# DM2080_RIGHT_OV9782.net
KiCad netlist of a schematic drawn in Altium Designer
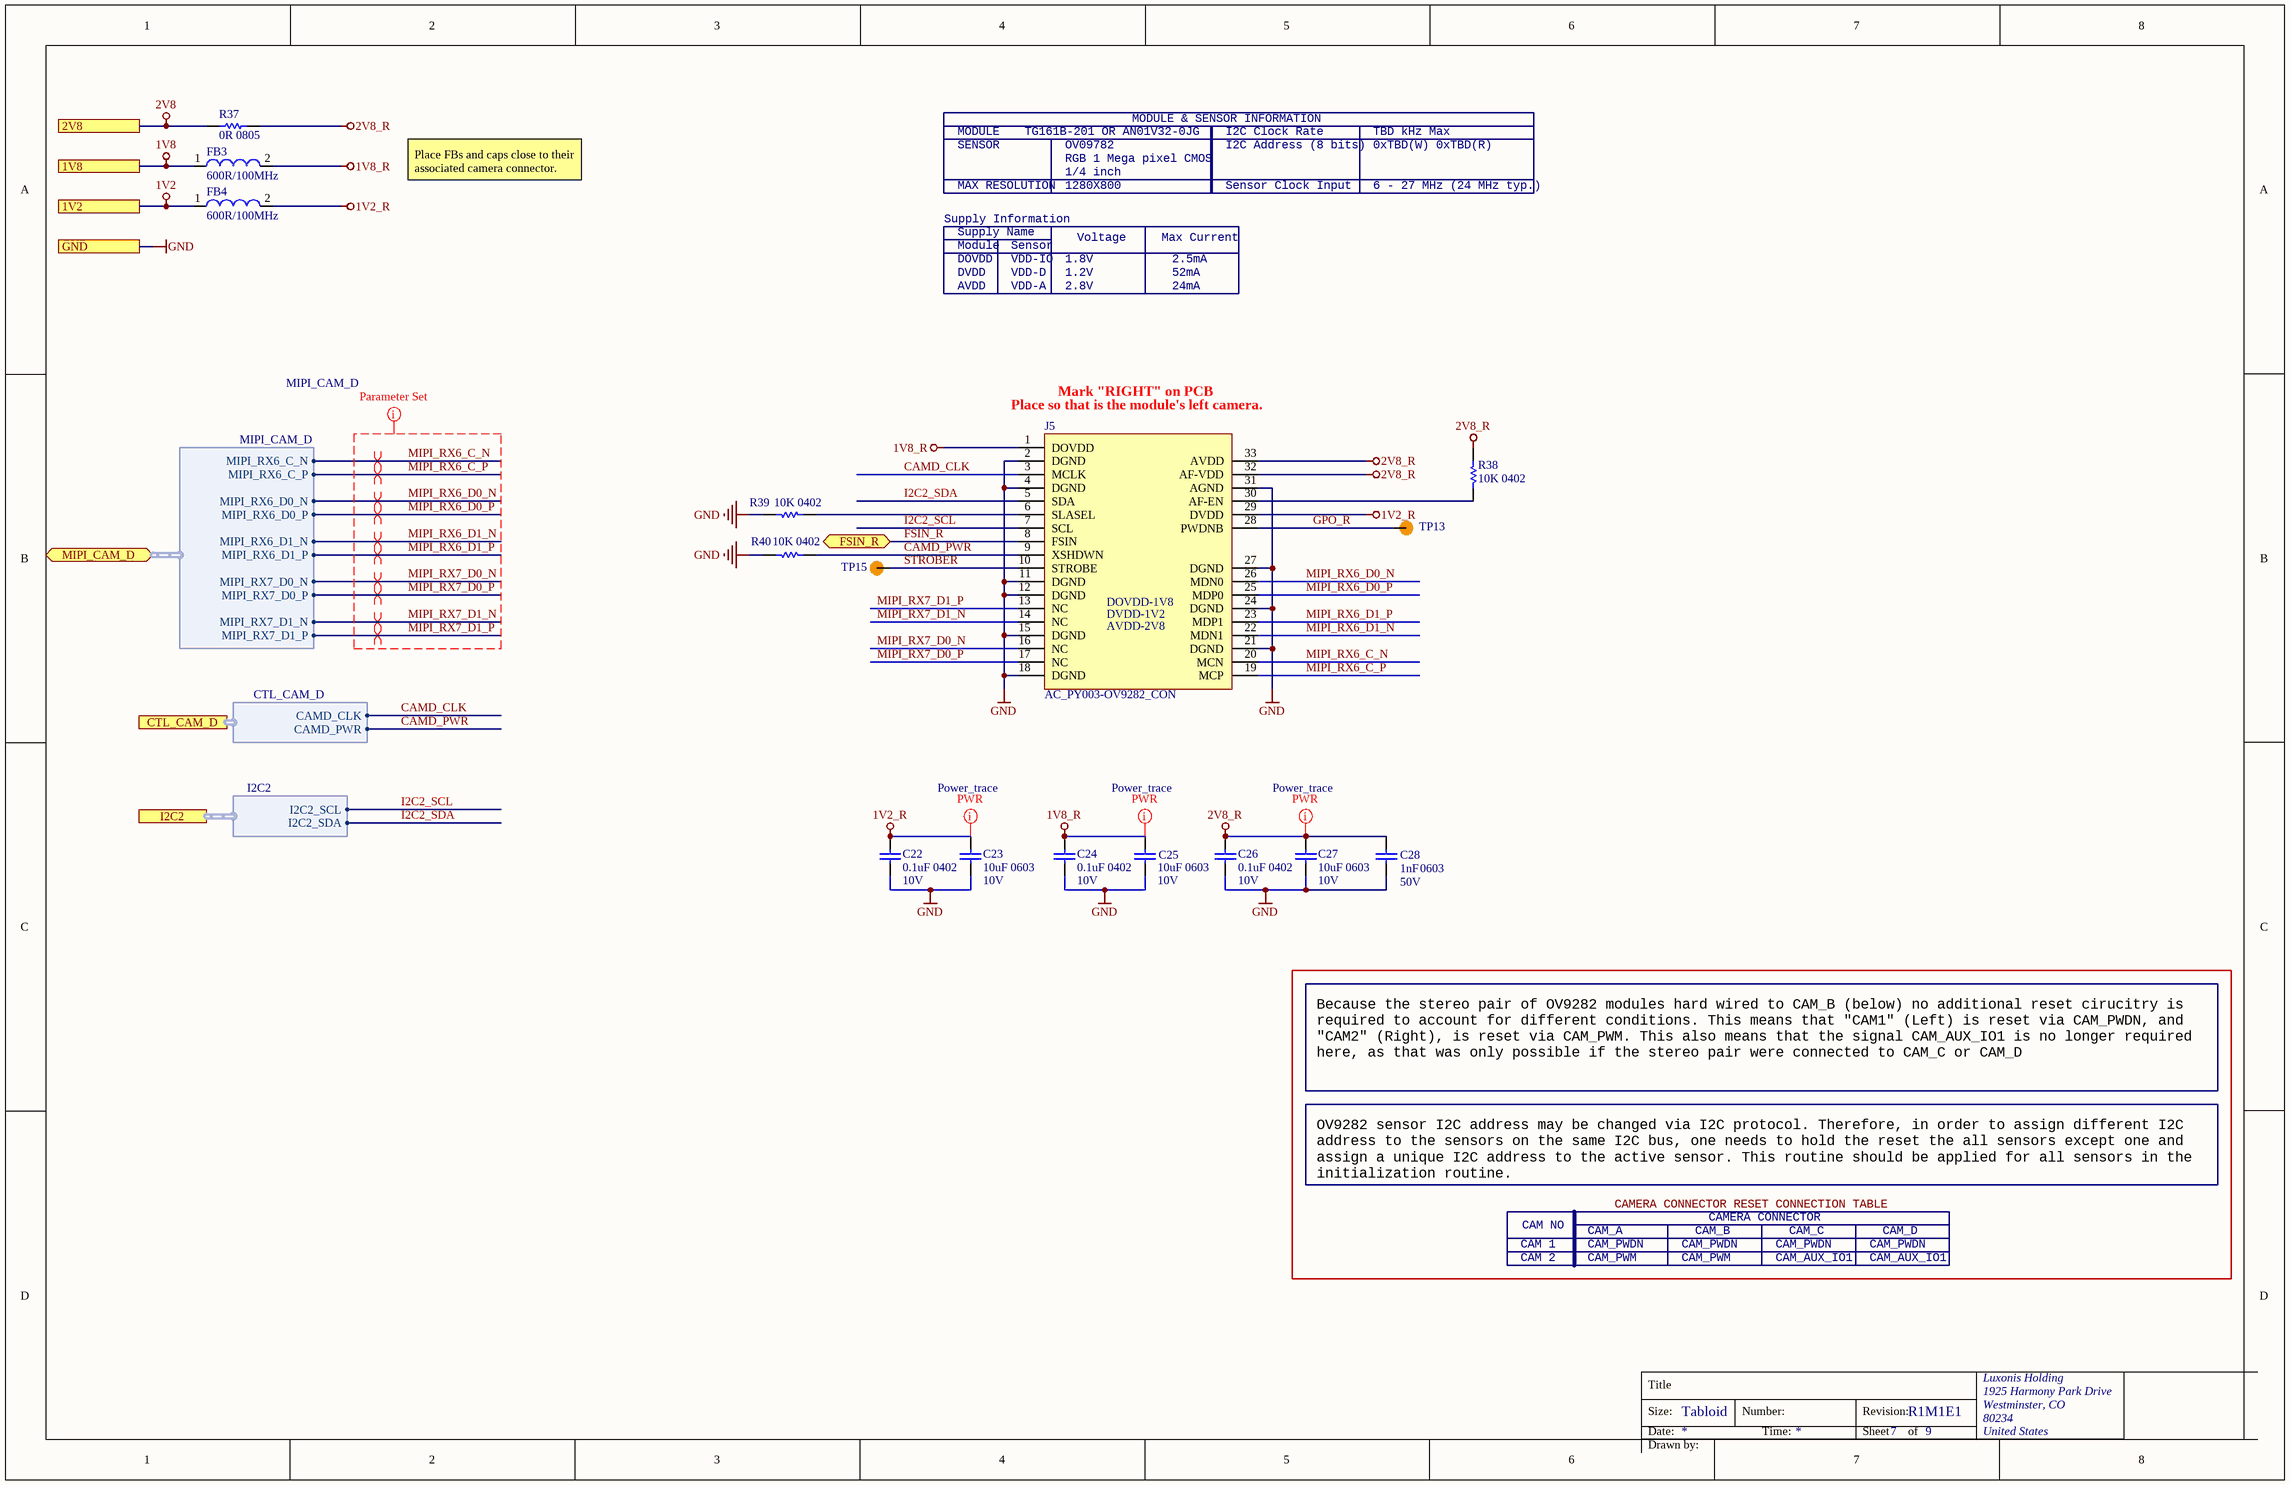
[diagram p0: DM2080_RIGHT_OV9782.SchDoc]

(export (version "E")
  (design (tool "Eeschema 10.0.6"))
  (components
    (comp (ref "C22")
      (value "0.1uF 0402")
      (footprint "CAP_Altium_Vault_Generic:CAPC0402(1005)70_L")
      (description "CAP CER 0.1UF 10V X7R 0402 5%")
      (fields (field (name "TOLERANCE") "5%") (field (name "VOLTAGE RATING") "10V"))
      (libsource (lib "LuxonisMaster") (part "GRM155R71A104JA01D"))
    )
    (comp (ref "C23")
      (value "10uF 0603")
      (footprint "CAP_Altium_Vault_Generic:CAPC0603(1608)100_L")
      (description "CAP CER 10UF 10V X5R 0603 20%")
      (fields (field (name "TOLERANCE") "20%") (field (name "VOLTAGE RATING") "10V"))
      (libsource (lib "LuxonisMaster") (part "GRM188R61A106ME69D"))
    )
    (comp (ref "C24")
      (value "0.1uF 0402")
      (footprint "CAP_Altium_Vault_Generic:CAPC0402(1005)70_L")
      (description "CAP CER 0.1UF 10V X7R 0402 5%")
      (fields (field (name "TOLERANCE") "5%") (field (name "VOLTAGE RATING") "10V"))
      (libsource (lib "LuxonisMaster") (part "GRM155R71A104JA01D"))
    )
    (comp (ref "C25")
      (value "10uF 0603")
      (footprint "CAP_Altium_Vault_Generic:CAPC0603(1608)100_L")
      (description "CAP CER 10UF 10V X5R 0603 20%")
      (fields (field (name "TOLERANCE") "20%") (field (name "VOLTAGE RATING") "10V"))
      (libsource (lib "LuxonisMaster") (part "GRM188R61A106ME69D"))
    )
    (comp (ref "C26")
      (value "0.1uF 0402")
      (footprint "CAP_Altium_Vault_Generic:CAPC0402(1005)70_L")
      (description "CAP CER 0.1UF 10V X7R 0402 5%")
      (fields (field (name "TOLERANCE") "5%") (field (name "VOLTAGE RATING") "10V"))
      (libsource (lib "LuxonisMaster") (part "GRM155R71A104JA01D"))
    )
    (comp (ref "C27")
      (value "10uF 0603")
      (footprint "CAP_Altium_Vault_Generic:CAPC0603(1608)100_L")
      (description "CAP CER 10UF 10V X5R 0603 20%")
      (fields (field (name "TOLERANCE") "20%") (field (name "VOLTAGE RATING") "10V"))
      (libsource (lib "LuxonisMaster") (part "GRM188R61A106ME69D"))
    )
    (comp (ref "C28")
      (value "1nF 0603 C0G")
      (footprint "CAP_Altium_Vault_Generic:CAPC0603(1608)100_L")
      (description "CAP CER 1000PF 50V C0G/NP0 0603")
      (fields
        (field (name "MANUFACTURER") "Murata")
        (field (name "MANUFACTURER PART NUMBER") "GRM1885C1H102FA01D")
        (field (name "CASE/PACKAGE") "0603")
        (field (name "CAPACITANCE") "1nF")
        (field (name "VOLTAGE RATING") "50V")
      )
      (libsource (lib "LuxonisMaster") (part "GRM1885C1H102FA01D"))
    )
    (comp (ref "FB3")
      (value "600R/100MHz")
      (footprint "LuxonisMaster:2508056017Y2")
      (description "FERRITE BEAD, 0.1OHM, 2A, 0805, 600R/100MHz")
      (fields (field (name "TOLERANCE") "25%"))
      (libsource (lib "LuxonisMaster") (part "2508056017Y2"))
    )
    (comp (ref "FB4")
      (value "600R/100MHz")
      (footprint "LuxonisMaster:2508056017Y2")
      (description "FERRITE BEAD, 0.1OHM, 2A, 0805, 600R/100MHz")
      (fields (field (name "TOLERANCE") "25%"))
      (libsource (lib "LuxonisMaster") (part "2508056017Y2"))
    )
    (comp (ref "J5")
      (value "AC_PY003-OV9282_CON")
      (footprint "AC-PY003-OV9282")
      (description "FFC/FPC Connector, 33 Contact(s), 1 Row(s), Female, Right Angle, Surface Mount Terminal")
      (libsource (lib "Luxonis LLC") (part "AC_PY003-OV9282_CON"))
    )
    (comp (ref "R37")
      (value "0R 0805")
      (footprint "RESC0805(2012)_L")
      (description "RES SMD 0.0R OHM 1% 1/8W 0805")
      (libsource (lib "LuxonisMaster") (part "CRCW08050000Z0EA"))
    )
    (comp (ref "R38")
      (value "10K 0402")
      (footprint "RES_Altium_Vault_Generic:RESC0402(1005)_L")
      (fields (field (name "TOLERANCE") "1%"))
      (libsource (lib "LuxonisMaster") (part "RC0402FR-1310KL"))
    )
    (comp (ref "R39")
      (value "10K 0402")
      (footprint "RES_Altium_Vault_Generic:RESC0402(1005)_L")
      (fields (field (name "TOLERANCE") "1%"))
      (libsource (lib "LuxonisMaster") (part "RC0402FR-1310KL"))
    )
    (comp (ref "R40")
      (value "10K 0402")
      (footprint "RES_Altium_Vault_Generic:RESC0402(1005)_L")
      (fields (field (name "TOLERANCE") "1%"))
      (libsource (lib "LuxonisMaster") (part "RC0402FR-1310KL"))
    )
    (comp (ref "TP13")
      (value "TP100_200_NS")
      (footprint "LuxonisMaster:TP100_200_NS")
      (libsource (lib "LuxonisMaster") (part "TEST_POINT"))
    )
    (comp (ref "TP15")
      (value "TP100_200_NS")
      (footprint "LuxonisMaster:TP100_200_NS")
      (libsource (lib "LuxonisMaster") (part "TEST_POINT"))
    )
  )
  (nets
    (net (code "4") (name "/CAMD_CLK") (class "Default")
      (node (ref "J5") (pin "3") (pinfunction "MCLK_3") (pintype "passive"))
    )
    (net (code "5") (name "/CAMD_PWR") (class "Default")
      (node (ref "J5") (pin "9") (pinfunction "XSHDWN_9") (pintype "passive"))
      (node (ref "R40") (pin "1") (pinfunction "1_1") (pintype "passive"))
    )
    (net (code "6") (name "/FSIN_R") (class "Default")
      (node (ref "J5") (pin "8") (pinfunction "FSIN_8") (pintype "passive"))
    )
    (net (code "7") (name "/GPO_R") (class "Default")
      (node (ref "J5") (pin "28") (pinfunction "PWDNB_28") (pintype "passive"))
      (node (ref "TP13") (pin "1") (pintype "passive"))
    )
    (net (code "8") (name "/I2C2_SCL") (class "Default")
      (node (ref "J5") (pin "7") (pinfunction "SCL_7") (pintype "passive"))
    )
    (net (code "9") (name "/I2C2_SDA") (class "Default")
      (node (ref "J5") (pin "5") (pinfunction "SDA_5") (pintype "passive"))
    )
    (net (code "10") (name "/MIPI_RX6_C_N") (class "Default")
      (node (ref "J5") (pin "20") (pinfunction "MCN_20") (pintype "passive"))
    )
    (net (code "11") (name "/MIPI_RX6_C_P") (class "Default")
      (node (ref "J5") (pin "19") (pinfunction "MCP_19") (pintype "passive"))
    )
    (net (code "12") (name "/MIPI_RX6_D0_N") (class "Default")
      (node (ref "J5") (pin "26") (pinfunction "MDN0_26") (pintype "passive"))
    )
    (net (code "13") (name "/MIPI_RX6_D0_P") (class "Default")
      (node (ref "J5") (pin "25") (pinfunction "MDP0_25") (pintype "passive"))
    )
    (net (code "14") (name "/MIPI_RX6_D1_N") (class "Default")
      (node (ref "J5") (pin "22") (pinfunction "MDN1_22") (pintype "passive"))
    )
    (net (code "15") (name "/MIPI_RX6_D1_P") (class "Default")
      (node (ref "J5") (pin "23") (pinfunction "MDP1_23") (pintype "passive"))
    )
    (net (code "16") (name "/MIPI_RX7_D0_N") (class "Default")
      (node (ref "J5") (pin "16") (pinfunction "NC_16") (pintype "passive"))
    )
    (net (code "17") (name "/MIPI_RX7_D0_P") (class "Default")
      (node (ref "J5") (pin "17") (pinfunction "NC_17") (pintype "passive"))
    )
    (net (code "18") (name "/MIPI_RX7_D1_N") (class "Default")
      (node (ref "J5") (pin "14") (pinfunction "NC_14") (pintype "passive"))
    )
    (net (code "19") (name "/MIPI_RX7_D1_P") (class "Default")
      (node (ref "J5") (pin "13") (pinfunction "NC_13") (pintype "passive"))
    )
    (net (code "20") (name "/STROBER") (class "Default")
      (node (ref "J5") (pin "10") (pinfunction "STROBE_10") (pintype "passive"))
      (node (ref "TP15") (pin "1") (pintype "passive"))
    )
    (net (code "24") (name "1V2") (class "Default")
      (node (ref "FB4") (pin "1") (pinfunction "1_1") (pintype "passive"))
    )
    (net (code "25") (name "1V2_R") (class "Default")
      (node (ref "C22") (pin "2") (pinfunction "2_2") (pintype "passive"))
      (node (ref "C23") (pin "2") (pinfunction "2_2") (pintype "passive"))
      (node (ref "FB4") (pin "2") (pinfunction "2_2") (pintype "passive"))
      (node (ref "J5") (pin "29") (pinfunction "DVDD_29") (pintype "passive"))
    )
    (net (code "26") (name "1V8") (class "Default")
      (node (ref "FB3") (pin "1") (pinfunction "1_1") (pintype "passive"))
    )
    (net (code "27") (name "1V8_R") (class "Default")
      (node (ref "C24") (pin "2") (pinfunction "2_2") (pintype "passive"))
      (node (ref "C25") (pin "2") (pinfunction "2_2") (pintype "passive"))
      (node (ref "FB3") (pin "2") (pinfunction "2_2") (pintype "passive"))
      (node (ref "J5") (pin "1") (pinfunction "DOVDD_1") (pintype "passive"))
    )
    (net (code "28") (name "2V8") (class "Default")
      (node (ref "R37") (pin "1") (pinfunction "1_1") (pintype "passive"))
    )
    (net (code "29") (name "2V8_R") (class "Default")
      (node (ref "C26") (pin "2") (pinfunction "2_2") (pintype "passive"))
      (node (ref "C27") (pin "2") (pinfunction "2_2") (pintype "passive"))
      (node (ref "C28") (pin "2") (pinfunction "2_2") (pintype "passive"))
      (node (ref "J5") (pin "32") (pinfunction "AF-VDD_32") (pintype "passive"))
      (node (ref "J5") (pin "33") (pinfunction "AVDD_33") (pintype "passive"))
      (node (ref "R37") (pin "2") (pinfunction "2_2") (pintype "passive"))
      (node (ref "R38") (pin "1") (pinfunction "1_1") (pintype "passive"))
    )
    (net (code "30") (name "GND") (class "Default")
      (node (ref "C22") (pin "1") (pinfunction "1_1") (pintype "passive"))
      (node (ref "C23") (pin "1") (pinfunction "1_1") (pintype "passive"))
      (node (ref "C24") (pin "1") (pinfunction "1_1") (pintype "passive"))
      (node (ref "C25") (pin "1") (pinfunction "1_1") (pintype "passive"))
      (node (ref "C26") (pin "1") (pinfunction "1_1") (pintype "passive"))
      (node (ref "C27") (pin "1") (pinfunction "1_1") (pintype "passive"))
      (node (ref "C28") (pin "1") (pinfunction "1_1") (pintype "passive"))
      (node (ref "J5") (pin "11") (pinfunction "DGND_11") (pintype "passive"))
      (node (ref "J5") (pin "12") (pinfunction "DGND_12") (pintype "passive"))
      (node (ref "J5") (pin "15") (pinfunction "DGND_15") (pintype "passive"))
      (node (ref "J5") (pin "18") (pinfunction "DGND_18") (pintype "passive"))
      (node (ref "J5") (pin "2") (pinfunction "DGND_2") (pintype "passive"))
      (node (ref "J5") (pin "21") (pinfunction "DGND_21") (pintype "passive"))
      (node (ref "J5") (pin "24") (pinfunction "DGND_24") (pintype "passive"))
      (node (ref "J5") (pin "27") (pinfunction "DGND_27") (pintype "passive"))
      (node (ref "J5") (pin "31") (pinfunction "AGND_31") (pintype "passive"))
      (node (ref "J5") (pin "4") (pinfunction "DGND_4") (pintype "passive"))
      (node (ref "R39") (pin "2") (pinfunction "2_2") (pintype "passive"))
      (node (ref "R40") (pin "2") (pinfunction "2_2") (pintype "passive"))
    )
    (net (code "31") (name "Net-(J5-AF-EN)") (class "Default")
      (node (ref "J5") (pin "30") (pinfunction "AF-EN_30") (pintype "passive"))
      (node (ref "R38") (pin "2") (pinfunction "2_2") (pintype "passive"))
    )
    (net (code "32") (name "Net-(J5-SLASEL)") (class "Default")
      (node (ref "J5") (pin "6") (pinfunction "SLASEL_6") (pintype "passive"))
      (node (ref "R39") (pin "1") (pinfunction "1_1") (pintype "passive"))
    )
  )
)
